# 5_cyber60-mx_periferals.net
KiCad netlist of a schematic drawn in Altium Designer
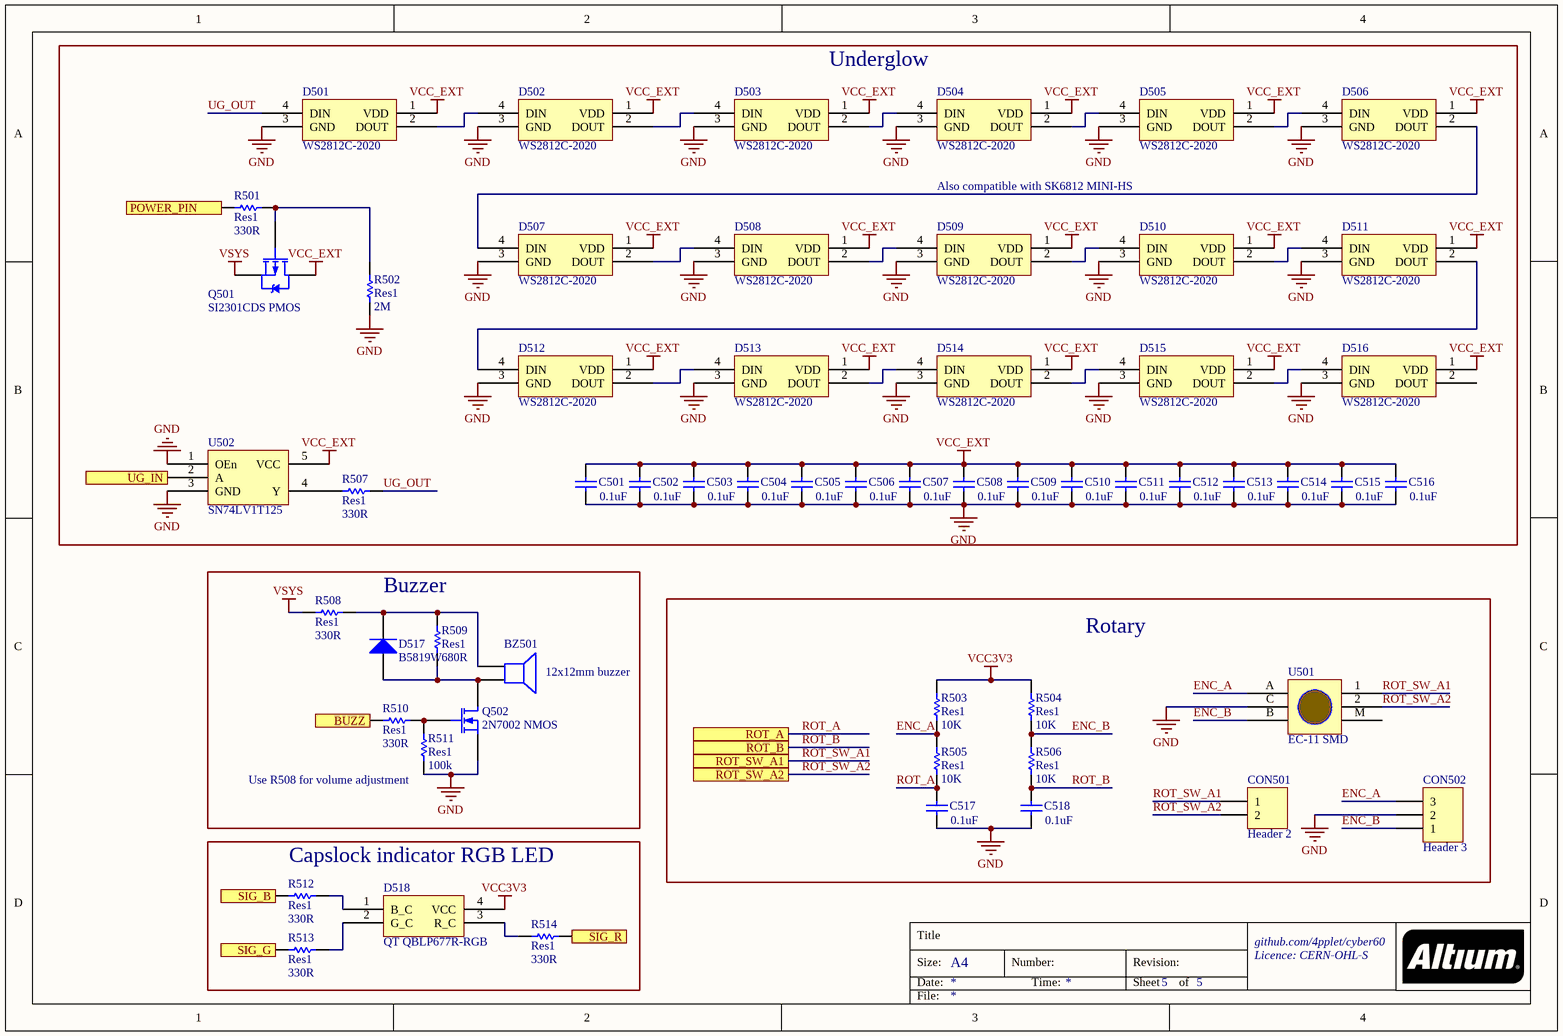
[diagram p0: 5_cyber60-mx_periferals.SchDoc]

(export (version "E")
  (design (tool "Eeschema 10.0.6"))
  (components
    (comp (ref "BZ501")
      (value "12x12mm buzzer")
      (footprint "buzzer 12x12")
      (description "Loudspeaker")
      (fields (field (name "LCSC PART #") "C409829") (field (name "MRF.PART") "YS-SBZ1230"))
      (libsource (lib "Miscellaneous Devices") (part "Speaker"))
    )
    (comp (ref "C501")
      (value "0.1uF")
      (footprint "C0603[1608]")
      (description "Capacitor")
      (fields (field (name "MFG") "KEMET") (field (name "LCSC PART #") "C14663"))
      (libsource (lib "Miscellaneous Devices") (part "Cap"))
    )
    (comp (ref "C502")
      (value "0.1uF")
      (footprint "C0603[1608]")
      (description "Capacitor")
      (fields (field (name "MFG") "KEMET") (field (name "LCSC PART #") "C14663"))
      (libsource (lib "Miscellaneous Devices") (part "Cap"))
    )
    (comp (ref "C503")
      (value "0.1uF")
      (footprint "C0603[1608]")
      (description "Capacitor")
      (fields (field (name "MFG") "KEMET") (field (name "LCSC PART #") "C14663"))
      (libsource (lib "Miscellaneous Devices") (part "Cap"))
    )
    (comp (ref "C504")
      (value "0.1uF")
      (footprint "C0603[1608]")
      (description "Capacitor")
      (fields (field (name "MFG") "KEMET") (field (name "LCSC PART #") "C14663"))
      (libsource (lib "Miscellaneous Devices") (part "Cap"))
    )
    (comp (ref "C505")
      (value "0.1uF")
      (footprint "C0603[1608]")
      (description "Capacitor")
      (fields (field (name "MFG") "KEMET") (field (name "LCSC PART #") "C14663"))
      (libsource (lib "Miscellaneous Devices") (part "Cap"))
    )
    (comp (ref "C506")
      (value "0.1uF")
      (footprint "C0603[1608]")
      (description "Capacitor")
      (fields (field (name "MFG") "KEMET") (field (name "LCSC PART #") "C14663"))
      (libsource (lib "Miscellaneous Devices") (part "Cap"))
    )
    (comp (ref "C507")
      (value "0.1uF")
      (footprint "C0603[1608]")
      (description "Capacitor")
      (fields (field (name "MFG") "KEMET") (field (name "LCSC PART #") "C14663"))
      (libsource (lib "Miscellaneous Devices") (part "Cap"))
    )
    (comp (ref "C508")
      (value "0.1uF")
      (footprint "C0603[1608]")
      (description "Capacitor")
      (fields (field (name "MFG") "KEMET") (field (name "LCSC PART #") "C14663"))
      (libsource (lib "Miscellaneous Devices") (part "Cap"))
    )
    (comp (ref "C509")
      (value "0.1uF")
      (footprint "C0603[1608]")
      (description "Capacitor")
      (fields (field (name "MFG") "KEMET") (field (name "LCSC PART #") "C14663"))
      (libsource (lib "Miscellaneous Devices") (part "Cap"))
    )
    (comp (ref "C510")
      (value "0.1uF")
      (footprint "C0603[1608]")
      (description "Capacitor")
      (fields (field (name "MFG") "KEMET") (field (name "LCSC PART #") "C14663"))
      (libsource (lib "Miscellaneous Devices") (part "Cap"))
    )
    (comp (ref "C511")
      (value "0.1uF")
      (footprint "C0603[1608]")
      (description "Capacitor")
      (fields (field (name "MFG") "KEMET") (field (name "LCSC PART #") "C14663"))
      (libsource (lib "Miscellaneous Devices") (part "Cap"))
    )
    (comp (ref "C512")
      (value "0.1uF")
      (footprint "C0603[1608]")
      (description "Capacitor")
      (fields (field (name "MFG") "KEMET") (field (name "LCSC PART #") "C14663"))
      (libsource (lib "Miscellaneous Devices") (part "Cap"))
    )
    (comp (ref "C513")
      (value "0.1uF")
      (footprint "C0603[1608]")
      (description "Capacitor")
      (fields (field (name "MFG") "KEMET") (field (name "LCSC PART #") "C14663"))
      (libsource (lib "Miscellaneous Devices") (part "Cap"))
    )
    (comp (ref "C514")
      (value "0.1uF")
      (footprint "C0603[1608]")
      (description "Capacitor")
      (fields (field (name "MFG") "KEMET") (field (name "LCSC PART #") "C14663"))
      (libsource (lib "Miscellaneous Devices") (part "Cap"))
    )
    (comp (ref "C515")
      (value "0.1uF")
      (footprint "C0603[1608]")
      (description "Capacitor")
      (fields (field (name "MFG") "KEMET") (field (name "LCSC PART #") "C14663"))
      (libsource (lib "Miscellaneous Devices") (part "Cap"))
    )
    (comp (ref "C516")
      (value "0.1uF")
      (footprint "C0603[1608]")
      (description "Capacitor")
      (fields (field (name "MFG") "KEMET") (field (name "LCSC PART #") "C14663"))
      (libsource (lib "Miscellaneous Devices") (part "Cap"))
    )
    (comp (ref "C517")
      (value "0.1uF")
      (footprint "C0603[1608]")
      (description "Capacitor")
      (fields (field (name "MFG") "KEMET") (field (name "LCSC PART #") "C14663"))
      (libsource (lib "Miscellaneous Devices") (part "Cap"))
    )
    (comp (ref "C518")
      (value "0.1uF")
      (footprint "C0603[1608]")
      (description "Capacitor")
      (fields (field (name "MFG") "KEMET") (field (name "LCSC PART #") "C14663"))
      (libsource (lib "Miscellaneous Devices") (part "Cap"))
    )
    (comp (ref "CON501")
      (value "Header 2")
      (footprint "HDR1X2")
      (description "Header, 2-Pin")
      (libsource (lib "Miscellaneous Connectors") (part "Header 2"))
    )
    (comp (ref "CON502")
      (value "Header 3")
      (footprint "HDR1X3")
      (description "Header, 3-Pin")
      (libsource (lib "Miscellaneous Connectors") (part "Header 3"))
    )
    (comp (ref "D501")
      (value "WS2812C-2020")
      (footprint "WS2812B - 2020")
      (fields (field (name "LCSC PART #") "C965556"))
      (libsource (lib "Keebs") (part "WS2812B"))
    )
    (comp (ref "D502")
      (value "WS2812C-2020")
      (footprint "WS2812B - 2020")
      (fields (field (name "LCSC PART #") "C965556"))
      (libsource (lib "Keebs") (part "WS2812B"))
    )
    (comp (ref "D503")
      (value "WS2812C-2020")
      (footprint "WS2812B - 2020")
      (fields (field (name "LCSC PART #") "C965556"))
      (libsource (lib "Keebs") (part "WS2812B"))
    )
    (comp (ref "D504")
      (value "WS2812C-2020")
      (footprint "WS2812B - 2020")
      (fields (field (name "LCSC PART #") "C965556"))
      (libsource (lib "Keebs") (part "WS2812B"))
    )
    (comp (ref "D505")
      (value "WS2812C-2020")
      (footprint "WS2812B - 2020")
      (fields (field (name "LCSC PART #") "C965556"))
      (libsource (lib "Keebs") (part "WS2812B"))
    )
    (comp (ref "D506")
      (value "WS2812C-2020")
      (footprint "WS2812B - 2020")
      (fields (field (name "LCSC PART #") "C965556"))
      (libsource (lib "Keebs") (part "WS2812B"))
    )
    (comp (ref "D507")
      (value "WS2812C-2020")
      (footprint "WS2812B - 2020")
      (fields (field (name "LCSC PART #") "C965556"))
      (libsource (lib "Keebs") (part "WS2812B"))
    )
    (comp (ref "D508")
      (value "WS2812C-2020")
      (footprint "WS2812B - 2020")
      (fields (field (name "LCSC PART #") "C965556"))
      (libsource (lib "Keebs") (part "WS2812B"))
    )
    (comp (ref "D509")
      (value "WS2812C-2020")
      (footprint "WS2812B - 2020")
      (fields (field (name "LCSC PART #") "C965556"))
      (libsource (lib "Keebs") (part "WS2812B"))
    )
    (comp (ref "D510")
      (value "WS2812C-2020")
      (footprint "WS2812B - 2020")
      (fields (field (name "LCSC PART #") "C965556"))
      (libsource (lib "Keebs") (part "WS2812B"))
    )
    (comp (ref "D511")
      (value "WS2812C-2020")
      (footprint "WS2812B - 2020")
      (fields (field (name "LCSC PART #") "C965556"))
      (libsource (lib "Keebs") (part "WS2812B"))
    )
    (comp (ref "D512")
      (value "WS2812C-2020")
      (footprint "WS2812B - 2020")
      (fields (field (name "LCSC PART #") "C965556"))
      (libsource (lib "Keebs") (part "WS2812B"))
    )
    (comp (ref "D513")
      (value "WS2812C-2020")
      (footprint "WS2812B - 2020")
      (fields (field (name "LCSC PART #") "C965556"))
      (libsource (lib "Keebs") (part "WS2812B"))
    )
    (comp (ref "D514")
      (value "WS2812C-2020")
      (footprint "WS2812B - 2020")
      (fields (field (name "LCSC PART #") "C965556"))
      (libsource (lib "Keebs") (part "WS2812B"))
    )
    (comp (ref "D515")
      (value "WS2812C-2020")
      (footprint "WS2812B - 2020")
      (fields (field (name "LCSC PART #") "C965556"))
      (libsource (lib "Keebs") (part "WS2812B"))
    )
    (comp (ref "D516")
      (value "WS2812C-2020")
      (footprint "WS2812B - 2020")
      (fields (field (name "LCSC PART #") "C965556"))
      (libsource (lib "Keebs") (part "WS2812B"))
    )
    (comp (ref "D517")
      (value "B5819W")
      (footprint "SOD-123")
      (description "Default Diode")
      (fields (field (name "LCSC PART #") "C8598"))
      (libsource (lib "Miscellaneous Devices") (part "Diode"))
    )
    (comp (ref "D518")
      (value "QT QBLP677R-RGB")
      (footprint "QT QBLP677R-RGB")
      (description "RGB LED")
      (fields (field (name "MFG") "QT Brightek (QTB)"))
      (libsource (lib "Keebs") (part "QT QBLP677R-RGB"))
    )
    (comp (ref "Q501")
      (value "SI2301CDS PMOS")
      (footprint "SOT-23-3")
      (description "P-Channel Power MOSFET")
      (fields (field (name "MRF.PART") "SI2301CDS-T1-GE3") (field (name "LCSC PART #") "C10487"))
      (libsource (lib "Miscellaneous Devices") (part "PMOS-2"))
    )
    (comp (ref "Q502")
      (value "2N7002 NMOS")
      (footprint "SOT-23-3")
      (description "N-Channel MOSFET")
      (fields (field (name "LCSC PART #") "C8545") (field (name "MRF.PART") "2N7002"))
      (libsource (lib "Miscellaneous Devices") (part "MOSFET-N"))
    )
    (comp (ref "R501")
      (value "Res1")
      (footprint "R0603[1608]")
      (description "Resistor")
      (fields
        (field (name "ALTIUM_VALUE") "330R")
        (field (name "LCSC PART #") "C23138")
        (field (name "MRF.PART") "0603WAF3300T5E")
      )
      (libsource (lib "Miscellaneous Devices") (part "Res1"))
    )
    (comp (ref "R502")
      (value "Res1")
      (footprint "R0603[1608]")
      (description "Resistor")
      (fields
        (field (name "ALTIUM_VALUE") "2M")
        (field (name "MRF.PART") "0603WAF2004T5E")
        (field (name "LCSC PART #") "C22976")
      )
      (libsource (lib "Miscellaneous Devices") (part "Res1"))
    )
    (comp (ref "R503")
      (value "Res1")
      (footprint "R0603[1608]")
      (description "Resistor")
      (fields
        (field (name "ALTIUM_VALUE") "10K")
        (field (name "MRF.PART") "0603WAF1002T5E")
        (field (name "LCSC PART #") "C25804")
      )
      (libsource (lib "Miscellaneous Devices") (part "Res1"))
    )
    (comp (ref "R504")
      (value "Res1")
      (footprint "R0603[1608]")
      (description "Resistor")
      (fields
        (field (name "ALTIUM_VALUE") "10K")
        (field (name "MRF.PART") "0603WAF1002T5E")
        (field (name "LCSC PART #") "C25804")
      )
      (libsource (lib "Miscellaneous Devices") (part "Res1"))
    )
    (comp (ref "R505")
      (value "Res1")
      (footprint "R0603[1608]")
      (description "Resistor")
      (fields
        (field (name "ALTIUM_VALUE") "10K")
        (field (name "MRF.PART") "0603WAF1002T5E")
        (field (name "LCSC PART #") "C25804")
      )
      (libsource (lib "Miscellaneous Devices") (part "Res1"))
    )
    (comp (ref "R506")
      (value "Res1")
      (footprint "R0603[1608]")
      (description "Resistor")
      (fields
        (field (name "ALTIUM_VALUE") "10K")
        (field (name "MRF.PART") "0603WAF1002T5E")
        (field (name "LCSC PART #") "C25804")
      )
      (libsource (lib "Miscellaneous Devices") (part "Res1"))
    )
    (comp (ref "R507")
      (value "Res1")
      (footprint "R0603[1608]")
      (description "Resistor")
      (fields
        (field (name "ALTIUM_VALUE") "330R")
        (field (name "LCSC PART #") "C23138")
        (field (name "MRF.PART") "0603WAF3300T5E")
      )
      (libsource (lib "Miscellaneous Devices") (part "Res1"))
    )
    (comp (ref "R508")
      (value "Res1")
      (footprint "R0603[1608]")
      (description "Resistor")
      (fields
        (field (name "ALTIUM_VALUE") "330R")
        (field (name "LCSC PART #") "C23138")
        (field (name "MRF.PART") "0603WAF3300T5E")
      )
      (libsource (lib "Miscellaneous Devices") (part "Res1"))
    )
    (comp (ref "R509")
      (value "Res1")
      (footprint "R0603[1608]")
      (description "Resistor")
      (fields
        (field (name "ALTIUM_VALUE") "680R")
        (field (name "MRF.PART") "0603WAF6800T5E")
        (field (name "LCSC PART #") "C23228")
      )
      (libsource (lib "Miscellaneous Devices") (part "Res1"))
    )
    (comp (ref "R510")
      (value "Res1")
      (footprint "R0603[1608]")
      (description "Resistor")
      (fields
        (field (name "ALTIUM_VALUE") "330R")
        (field (name "LCSC PART #") "C23138")
        (field (name "MRF.PART") "0603WAF3300T5E")
      )
      (libsource (lib "Miscellaneous Devices") (part "Res1"))
    )
    (comp (ref "R511")
      (value "Res1")
      (footprint "R0603[1608]")
      (description "Resistor")
      (fields
        (field (name "ALTIUM_VALUE") "100k")
        (field (name "MRF.PART") "0603WAF1003T5E")
        (field (name "LCSC PART #") "C25803")
      )
      (libsource (lib "Miscellaneous Devices") (part "Res1"))
    )
    (comp (ref "R512")
      (value "Res1")
      (footprint "R0603[1608]")
      (description "Resistor")
      (fields
        (field (name "ALTIUM_VALUE") "330R")
        (field (name "LCSC PART #") "C23138")
        (field (name "MRF.PART") "0603WAF3300T5E")
      )
      (libsource (lib "Miscellaneous Devices") (part "Res1"))
    )
    (comp (ref "R513")
      (value "Res1")
      (footprint "R0603[1608]")
      (description "Resistor")
      (fields
        (field (name "ALTIUM_VALUE") "330R")
        (field (name "LCSC PART #") "C23138")
        (field (name "MRF.PART") "0603WAF3300T5E")
      )
      (libsource (lib "Miscellaneous Devices") (part "Res1"))
    )
    (comp (ref "R514")
      (value "Res1")
      (footprint "R0603[1608]")
      (description "Resistor")
      (fields
        (field (name "ALTIUM_VALUE") "330R")
        (field (name "LCSC PART #") "C23138")
        (field (name "MRF.PART") "0603WAF3300T5E")
      )
      (libsource (lib "Miscellaneous Devices") (part "Res1"))
    )
    (comp (ref "U501") (value "EC-11 SMD") (footprint "EC11-SMD") (libsource (lib "Keebs") (part "EC-11")))
    (comp (ref "U502")
      (value "SN74LV1T125")
      (footprint "SOT-23-5")
      (description "SN74LV1T125 or SN74LV1T34. Connect OE to GND")
      (fields (field (name "LCSC PART #") "C473338") (field (name "MRF.PART") "SN74LV1T125DBVR"))
      (libsource (lib "Keebs") (part "SN74LV1T125"))
    )
  )
  (nets
    (net (code "1") (name "/BUZZ") (class "Default")
      (node (ref "R510") (pin "2") (pinfunction "2_2") (pintype "passive"))
    )
    (net (code "2") (name "/ENC_A") (class "Default")
      (node (ref "CON502") (pin "3") (pinfunction "3_3") (pintype "passive"))
      (node (ref "R503") (pin "2") (pinfunction "2_2") (pintype "passive"))
      (node (ref "R505") (pin "1") (pinfunction "1_1") (pintype "passive"))
      (node (ref "U501") (pin "A") (pinfunction "B_A") (pintype "passive"))
    )
    (net (code "3") (name "/ENC_B") (class "Default")
      (node (ref "CON502") (pin "1") (pinfunction "1_1") (pintype "passive"))
      (node (ref "R504") (pin "2") (pinfunction "2_2") (pintype "passive"))
      (node (ref "R506") (pin "1") (pinfunction "1_1") (pintype "passive"))
      (node (ref "U501") (pin "B") (pinfunction "B_B") (pintype "passive"))
    )
    (net (code "4") (name "/POWER_PIN") (class "Default")
      (node (ref "R501") (pin "1") (pinfunction "1_1") (pintype "passive"))
    )
    (net (code "5") (name "/ROT_A") (class "Default")
      (node (ref "C517") (pin "2") (pinfunction "2_2") (pintype "passive"))
      (node (ref "R505") (pin "2") (pinfunction "2_2") (pintype "passive"))
    )
    (net (code "6") (name "/ROT_B") (class "Default")
      (node (ref "C518") (pin "2") (pinfunction "2_2") (pintype "passive"))
      (node (ref "R506") (pin "2") (pinfunction "2_2") (pintype "passive"))
    )
    (net (code "7") (name "/ROT_SW_A1") (class "Default")
      (node (ref "CON501") (pin "1") (pinfunction "1_1") (pintype "passive"))
      (node (ref "U501") (pin "1") (pinfunction "1_1") (pintype "passive"))
    )
    (net (code "8") (name "/ROT_SW_A2") (class "Default")
      (node (ref "CON501") (pin "2") (pinfunction "2_2") (pintype "passive"))
      (node (ref "U501") (pin "2") (pinfunction "2_2") (pintype "passive"))
    )
    (net (code "9") (name "/SIG_B") (class "Default")
      (node (ref "R512") (pin "2") (pinfunction "2_2") (pintype "passive"))
    )
    (net (code "10") (name "/SIG_G") (class "Default")
      (node (ref "R513") (pin "2") (pinfunction "2_2") (pintype "passive"))
    )
    (net (code "11") (name "/SIG_R") (class "Default")
      (node (ref "R514") (pin "1") (pinfunction "1_1") (pintype "passive"))
    )
    (net (code "12") (name "/UG_IN") (class "Default")
      (node (ref "U502") (pin "2") (pinfunction "A_2") (pintype "passive"))
    )
    (net (code "13") (name "/UG_OUT") (class "Default")
      (node (ref "D501") (pin "4") (pinfunction "DIN_4") (pintype "passive"))
      (node (ref "R507") (pin "1") (pinfunction "1_1") (pintype "passive"))
    )
    (net (code "14") (name "GND") (class "Default")
      (node (ref "C501") (pin "1") (pinfunction "1_1") (pintype "passive"))
      (node (ref "C502") (pin "1") (pinfunction "1_1") (pintype "passive"))
      (node (ref "C503") (pin "1") (pinfunction "1_1") (pintype "passive"))
      (node (ref "C504") (pin "1") (pinfunction "1_1") (pintype "passive"))
      (node (ref "C505") (pin "1") (pinfunction "1_1") (pintype "passive"))
      (node (ref "C506") (pin "1") (pinfunction "1_1") (pintype "passive"))
      (node (ref "C507") (pin "1") (pinfunction "1_1") (pintype "passive"))
      (node (ref "C508") (pin "1") (pinfunction "1_1") (pintype "passive"))
      (node (ref "C509") (pin "1") (pinfunction "1_1") (pintype "passive"))
      (node (ref "C510") (pin "1") (pinfunction "1_1") (pintype "passive"))
      (node (ref "C511") (pin "1") (pinfunction "1_1") (pintype "passive"))
      (node (ref "C512") (pin "1") (pinfunction "1_1") (pintype "passive"))
      (node (ref "C513") (pin "1") (pinfunction "1_1") (pintype "passive"))
      (node (ref "C514") (pin "1") (pinfunction "1_1") (pintype "passive"))
      (node (ref "C515") (pin "1") (pinfunction "1_1") (pintype "passive"))
      (node (ref "C516") (pin "1") (pinfunction "1_1") (pintype "passive"))
      (node (ref "C517") (pin "1") (pinfunction "1_1") (pintype "passive"))
      (node (ref "C518") (pin "1") (pinfunction "1_1") (pintype "passive"))
      (node (ref "CON502") (pin "2") (pinfunction "2_2") (pintype "passive"))
      (node (ref "D501") (pin "3") (pinfunction "GND_3") (pintype "passive"))
      (node (ref "D502") (pin "3") (pinfunction "GND_3") (pintype "passive"))
      (node (ref "D503") (pin "3") (pinfunction "GND_3") (pintype "passive"))
      (node (ref "D504") (pin "3") (pinfunction "GND_3") (pintype "passive"))
      (node (ref "D505") (pin "3") (pinfunction "GND_3") (pintype "passive"))
      (node (ref "D506") (pin "3") (pinfunction "GND_3") (pintype "passive"))
      (node (ref "D507") (pin "3") (pinfunction "GND_3") (pintype "passive"))
      (node (ref "D508") (pin "3") (pinfunction "GND_3") (pintype "passive"))
      (node (ref "D509") (pin "3") (pinfunction "GND_3") (pintype "passive"))
      (node (ref "D510") (pin "3") (pinfunction "GND_3") (pintype "passive"))
      (node (ref "D511") (pin "3") (pinfunction "GND_3") (pintype "passive"))
      (node (ref "D512") (pin "3") (pinfunction "GND_3") (pintype "passive"))
      (node (ref "D513") (pin "3") (pinfunction "GND_3") (pintype "passive"))
      (node (ref "D514") (pin "3") (pinfunction "GND_3") (pintype "passive"))
      (node (ref "D515") (pin "3") (pinfunction "GND_3") (pintype "passive"))
      (node (ref "D516") (pin "3") (pinfunction "GND_3") (pintype "passive"))
      (node (ref "Q502") (pin "2") (pinfunction "S_2") (pintype "passive"))
      (node (ref "R502") (pin "1") (pinfunction "1_1") (pintype "passive"))
      (node (ref "R511") (pin "2") (pinfunction "2_2") (pintype "passive"))
      (node (ref "U501") (pin "C") (pinfunction "C_C") (pintype "passive"))
      (node (ref "U502") (pin "1") (pinfunction "OEn_1") (pintype "passive"))
      (node (ref "U502") (pin "3") (pinfunction "GND_3") (pintype "passive"))
    )
    (net (code "15") (name "Net-(D501-DOUT)") (class "Default")
      (node (ref "D501") (pin "2") (pinfunction "DOUT_2") (pintype "passive"))
      (node (ref "D502") (pin "4") (pinfunction "DIN_4") (pintype "passive"))
    )
    (net (code "16") (name "Net-(D502-DOUT)") (class "Default")
      (node (ref "D502") (pin "2") (pinfunction "DOUT_2") (pintype "passive"))
      (node (ref "D503") (pin "4") (pinfunction "DIN_4") (pintype "passive"))
    )
    (net (code "17") (name "Net-(D503-DOUT)") (class "Default")
      (node (ref "D503") (pin "2") (pinfunction "DOUT_2") (pintype "passive"))
      (node (ref "D504") (pin "4") (pinfunction "DIN_4") (pintype "passive"))
    )
    (net (code "18") (name "Net-(D504-DOUT)") (class "Default")
      (node (ref "D504") (pin "2") (pinfunction "DOUT_2") (pintype "passive"))
      (node (ref "D505") (pin "4") (pinfunction "DIN_4") (pintype "passive"))
    )
    (net (code "19") (name "Net-(D505-DOUT)") (class "Default")
      (node (ref "D505") (pin "2") (pinfunction "DOUT_2") (pintype "passive"))
      (node (ref "D506") (pin "4") (pinfunction "DIN_4") (pintype "passive"))
    )
    (net (code "20") (name "Net-(D506-DOUT)") (class "Default")
      (node (ref "D506") (pin "2") (pinfunction "DOUT_2") (pintype "passive"))
      (node (ref "D507") (pin "4") (pinfunction "DIN_4") (pintype "passive"))
    )
    (net (code "21") (name "Net-(D507-DOUT)") (class "Default")
      (node (ref "D507") (pin "2") (pinfunction "DOUT_2") (pintype "passive"))
      (node (ref "D508") (pin "4") (pinfunction "DIN_4") (pintype "passive"))
    )
    (net (code "22") (name "Net-(D508-DOUT)") (class "Default")
      (node (ref "D508") (pin "2") (pinfunction "DOUT_2") (pintype "passive"))
      (node (ref "D509") (pin "4") (pinfunction "DIN_4") (pintype "passive"))
    )
    (net (code "23") (name "Net-(D509-DOUT)") (class "Default")
      (node (ref "D509") (pin "2") (pinfunction "DOUT_2") (pintype "passive"))
      (node (ref "D510") (pin "4") (pinfunction "DIN_4") (pintype "passive"))
    )
    (net (code "24") (name "Net-(D510-DOUT)") (class "Default")
      (node (ref "D510") (pin "2") (pinfunction "DOUT_2") (pintype "passive"))
      (node (ref "D511") (pin "4") (pinfunction "DIN_4") (pintype "passive"))
    )
    (net (code "25") (name "Net-(D511-DOUT)") (class "Default")
      (node (ref "D511") (pin "2") (pinfunction "DOUT_2") (pintype "passive"))
      (node (ref "D512") (pin "4") (pinfunction "DIN_4") (pintype "passive"))
    )
    (net (code "26") (name "Net-(D512-DOUT)") (class "Default")
      (node (ref "D512") (pin "2") (pinfunction "DOUT_2") (pintype "passive"))
      (node (ref "D513") (pin "4") (pinfunction "DIN_4") (pintype "passive"))
    )
    (net (code "27") (name "Net-(D513-DOUT)") (class "Default")
      (node (ref "D513") (pin "2") (pinfunction "DOUT_2") (pintype "passive"))
      (node (ref "D514") (pin "4") (pinfunction "DIN_4") (pintype "passive"))
    )
    (net (code "28") (name "Net-(D514-DOUT)") (class "Default")
      (node (ref "D514") (pin "2") (pinfunction "DOUT_2") (pintype "passive"))
      (node (ref "D515") (pin "4") (pinfunction "DIN_4") (pintype "passive"))
    )
    (net (code "29") (name "Net-(D515-DOUT)") (class "Default")
      (node (ref "D515") (pin "2") (pinfunction "DOUT_2") (pintype "passive"))
      (node (ref "D516") (pin "4") (pinfunction "DIN_4") (pintype "passive"))
    )
    (net (code "30") (name "Net-(D517-A)") (class "Default")
      (node (ref "BZ501") (pin "2") (pinfunction "2_2") (pintype "passive"))
      (node (ref "D517") (pin "1") (pinfunction "A_1") (pintype "passive"))
      (node (ref "Q502") (pin "3") (pinfunction "D_3") (pintype "passive"))
      (node (ref "R509") (pin "2") (pinfunction "2_2") (pintype "passive"))
    )
    (net (code "31") (name "Net-(D517-K)") (class "Default")
      (node (ref "BZ501") (pin "1") (pinfunction "1_1") (pintype "passive"))
      (node (ref "D517") (pin "2") (pinfunction "K_2") (pintype "passive"))
      (node (ref "R508") (pin "1") (pinfunction "1_1") (pintype "passive"))
      (node (ref "R509") (pin "1") (pinfunction "1_1") (pintype "passive"))
    )
    (net (code "32") (name "Net-(D518-B_C)") (class "Default")
      (node (ref "D518") (pin "1") (pinfunction "B_C_1") (pintype "passive"))
      (node (ref "R512") (pin "1") (pinfunction "1_1") (pintype "passive"))
    )
    (net (code "33") (name "Net-(D518-G_C)") (class "Default")
      (node (ref "D518") (pin "2") (pinfunction "G_C_2") (pintype "passive"))
      (node (ref "R513") (pin "1") (pinfunction "1_1") (pintype "passive"))
    )
    (net (code "34") (name "Net-(D518-R_C)") (class "Default")
      (node (ref "D518") (pin "3") (pinfunction "R_C_3") (pintype "passive"))
      (node (ref "R514") (pin "2") (pinfunction "2_2") (pintype "passive"))
    )
    (net (code "35") (name "Net-(Q501-G)") (class "Default")
      (node (ref "Q501") (pin "1") (pinfunction "G_1") (pintype "passive"))
      (node (ref "R501") (pin "2") (pinfunction "2_2") (pintype "passive"))
      (node (ref "R502") (pin "2") (pinfunction "2_2") (pintype "passive"))
    )
    (net (code "36") (name "Net-(Q502-G)") (class "Default")
      (node (ref "Q502") (pin "1") (pinfunction "G_1") (pintype "passive"))
      (node (ref "R510") (pin "1") (pinfunction "1_1") (pintype "passive"))
      (node (ref "R511") (pin "1") (pinfunction "1_1") (pintype "passive"))
    )
    (net (code "37") (name "Net-(U502-Y)") (class "Default")
      (node (ref "R507") (pin "2") (pinfunction "2_2") (pintype "passive"))
      (node (ref "U502") (pin "4") (pinfunction "Y_4") (pintype "passive"))
    )
    (net (code "38") (name "VCC3V3") (class "Default")
      (node (ref "D518") (pin "4") (pinfunction "VCC_4") (pintype "passive"))
      (node (ref "R503") (pin "1") (pinfunction "1_1") (pintype "passive"))
      (node (ref "R504") (pin "1") (pinfunction "1_1") (pintype "passive"))
    )
    (net (code "39") (name "VCC_EXT") (class "Default")
      (node (ref "C501") (pin "2") (pinfunction "2_2") (pintype "passive"))
      (node (ref "C502") (pin "2") (pinfunction "2_2") (pintype "passive"))
      (node (ref "C503") (pin "2") (pinfunction "2_2") (pintype "passive"))
      (node (ref "C504") (pin "2") (pinfunction "2_2") (pintype "passive"))
      (node (ref "C505") (pin "2") (pinfunction "2_2") (pintype "passive"))
      (node (ref "C506") (pin "2") (pinfunction "2_2") (pintype "passive"))
      (node (ref "C507") (pin "2") (pinfunction "2_2") (pintype "passive"))
      (node (ref "C508") (pin "2") (pinfunction "2_2") (pintype "passive"))
      (node (ref "C509") (pin "2") (pinfunction "2_2") (pintype "passive"))
      (node (ref "C510") (pin "2") (pinfunction "2_2") (pintype "passive"))
      (node (ref "C511") (pin "2") (pinfunction "2_2") (pintype "passive"))
      (node (ref "C512") (pin "2") (pinfunction "2_2") (pintype "passive"))
      (node (ref "C513") (pin "2") (pinfunction "2_2") (pintype "passive"))
      (node (ref "C514") (pin "2") (pinfunction "2_2") (pintype "passive"))
      (node (ref "C515") (pin "2") (pinfunction "2_2") (pintype "passive"))
      (node (ref "C516") (pin "2") (pinfunction "2_2") (pintype "passive"))
      (node (ref "D501") (pin "1") (pinfunction "VDD_1") (pintype "passive"))
      (node (ref "D502") (pin "1") (pinfunction "VDD_1") (pintype "passive"))
      (node (ref "D503") (pin "1") (pinfunction "VDD_1") (pintype "passive"))
      (node (ref "D504") (pin "1") (pinfunction "VDD_1") (pintype "passive"))
      (node (ref "D505") (pin "1") (pinfunction "VDD_1") (pintype "passive"))
      (node (ref "D506") (pin "1") (pinfunction "VDD_1") (pintype "passive"))
      (node (ref "D507") (pin "1") (pinfunction "VDD_1") (pintype "passive"))
      (node (ref "D508") (pin "1") (pinfunction "VDD_1") (pintype "passive"))
      (node (ref "D509") (pin "1") (pinfunction "VDD_1") (pintype "passive"))
      (node (ref "D510") (pin "1") (pinfunction "VDD_1") (pintype "passive"))
      (node (ref "D511") (pin "1") (pinfunction "VDD_1") (pintype "passive"))
      (node (ref "D512") (pin "1") (pinfunction "VDD_1") (pintype "passive"))
      (node (ref "D513") (pin "1") (pinfunction "VDD_1") (pintype "passive"))
      (node (ref "D514") (pin "1") (pinfunction "VDD_1") (pintype "passive"))
      (node (ref "D515") (pin "1") (pinfunction "VDD_1") (pintype "passive"))
      (node (ref "D516") (pin "1") (pinfunction "VDD_1") (pintype "passive"))
      (node (ref "Q501") (pin "3") (pinfunction "D_3") (pintype "passive"))
      (node (ref "U502") (pin "5") (pinfunction "VCC_5") (pintype "passive"))
    )
    (net (code "40") (name "VSYS") (class "Default")
      (node (ref "Q501") (pin "2") (pinfunction "S_2") (pintype "passive"))
      (node (ref "R508") (pin "2") (pinfunction "2_2") (pintype "passive"))
    )
    (net (code "41") (name "unconnected-(D516-DOUT-Pad2)") (class "Default")
      (node (ref "D516") (pin "2") (pinfunction "DOUT_2") (pintype "passive"))
    )
    (net (code "42") (name "unconnected-(U501-PadM)") (class "Default")
      (node (ref "U501") (pin "M") (pinfunction "M_M") (pintype "passive"))
    )
  )
)
